# dozimetr-1layer.net
KiCad netlist of a schematic drawn in EAGLE
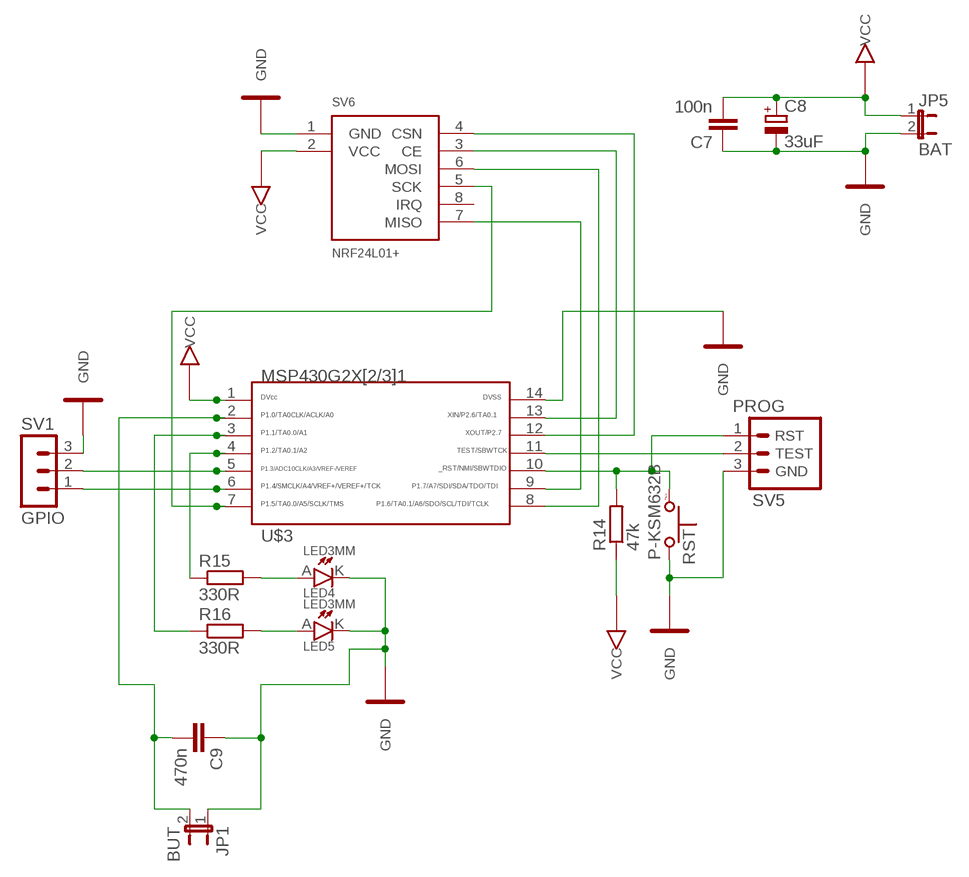
[diagram p0: schematic, sheet 1]

(export (version "E")
  (design (tool "Eeschema 10.0.6"))
  (components
    (comp (ref "C7")
      (value "100n")
      (footprint "eagle-import:C0805")
      (libsource (lib "eagle-import") (part "C-EUC0805"))
    )
    (comp (ref "C8")
      (value "33uF")
      (footprint "eagle-import:E2,5-6E")
      (libsource (lib "eagle-import") (part "CPOL-EUE2,5-6E"))
    )
    (comp (ref "C9")
      (value "470n")
      (footprint "eagle-import:C0805K")
      (libsource (lib "eagle-import") (part "C-EUC0805K"))
    )
    (comp (ref "JP1")
      (value "BUT")
      (footprint "eagle-import:JP1")
      (libsource (lib "eagle-import") (part "JP1E"))
    )
    (comp (ref "JP5")
      (value "BAT")
      (footprint "eagle-import:JP1")
      (libsource (lib "eagle-import") (part "JP1E"))
    )
    (comp (ref "LED4")
      (value "LED3MM")
      (footprint "eagle-import:LED3MM")
      (libsource (lib "eagle-import") (part "LED3MM"))
    )
    (comp (ref "LED5")
      (value "LED3MM")
      (footprint "eagle-import:LED3MM")
      (libsource (lib "eagle-import") (part "LED3MM"))
    )
    (comp (ref "R14")
      (value "47k")
      (footprint "eagle-import:R0805")
      (libsource (lib "eagle-import") (part "R-EU_R0805"))
    )
    (comp (ref "R15")
      (value "330R")
      (footprint "eagle-import:R0805")
      (libsource (lib "eagle-import") (part "R-EU_R0805"))
    )
    (comp (ref "R16")
      (value "330R")
      (footprint "eagle-import:R0805")
      (libsource (lib "eagle-import") (part "R-EU_R0805"))
    )
    (comp (ref "RST")
      (value "P-KSM632B")
      (footprint "eagle-import:P-KSM632B")
      (libsource (lib "eagle-import") (part "P-KSM632B"))
    )
    (comp (ref "SV1")
      (value "GPIO")
      (footprint "eagle-import:MA03-1")
      (libsource (lib "eagle-import") (part "con-lstb_MA03-1"))
    )
    (comp (ref "SV5")
      (value "PROG")
      (footprint "eagle-import:MA03-1")
      (libsource (lib "eagle-import") (part "MA03-1"))
    )
    (comp (ref "SV6")
      (value "NRF24L01+")
      (footprint "eagle-import:NRF24L01_MOD")
      (libsource (lib "eagle-import") (part "NRF24L01_MOD"))
    )
    (comp (ref "U$3")
      (value "G2X[2/3]1---PW14")
      (footprint "eagle-import:PW14")
      (libsource (lib "eagle-import") (part "G2X[2/3]1---PW14"))
    )
  )
  (nets
    (net (code "1") (name "GND") (class "Default")
      (node (ref "C7") (pin "1") (pinfunction "1_1") (pintype "passive"))
      (node (ref "C8") (pin "-") (pinfunction "-_-") (pintype "passive"))
      (node (ref "C9") (pin "1") (pinfunction "1_1") (pintype "passive"))
      (node (ref "JP1") (pin "1") (pinfunction "1_1") (pintype "passive"))
      (node (ref "JP5") (pin "2") (pinfunction "2_2") (pintype "passive"))
      (node (ref "LED4") (pin "K") (pinfunction "C_K") (pintype "bidirectional"))
      (node (ref "LED5") (pin "K") (pinfunction "C_K") (pintype "bidirectional"))
      (node (ref "RST") (pin "2") (pinfunction "2_2") (pintype "passive"))
      (node (ref "SV1") (pin "3") (pinfunction "3_3") (pintype "passive"))
      (node (ref "SV5") (pin "3") (pinfunction "GND_3") (pintype "passive"))
      (node (ref "SV6") (pin "1") (pinfunction "GND_1") (pintype "bidirectional"))
      (node (ref "U$3") (pin "14") (pinfunction "14_14") (pintype "bidirectional"))
    )
    (net (code "2") (name "Net-(C9-Pad2)") (class "Default")
      (node (ref "C9") (pin "2") (pinfunction "2_2") (pintype "passive"))
      (node (ref "JP1") (pin "2") (pinfunction "2_2") (pintype "passive"))
      (node (ref "U$3") (pin "2") (pinfunction "2_2") (pintype "bidirectional"))
    )
    (net (code "3") (name "Net-(LED4-PadA)") (class "Default")
      (node (ref "LED4") (pin "A") (pinfunction "A_A") (pintype "bidirectional"))
      (node (ref "R15") (pin "2") (pinfunction "2_2") (pintype "passive"))
    )
    (net (code "4") (name "Net-(LED5-PadA)") (class "Default")
      (node (ref "LED5") (pin "A") (pinfunction "A_A") (pintype "bidirectional"))
      (node (ref "R16") (pin "2") (pinfunction "2_2") (pintype "passive"))
    )
    (net (code "5") (name "Net-(R15-Pad1)") (class "Default")
      (node (ref "R15") (pin "1") (pinfunction "1_1") (pintype "passive"))
      (node (ref "U$3") (pin "4") (pinfunction "4_4") (pintype "bidirectional"))
    )
    (net (code "6") (name "Net-(R16-Pad1)") (class "Default")
      (node (ref "R16") (pin "1") (pinfunction "1_1") (pintype "passive"))
      (node (ref "U$3") (pin "3") (pinfunction "3_3") (pintype "bidirectional"))
    )
    (net (code "7") (name "Net-(SV1-Pad1)") (class "Default")
      (node (ref "SV1") (pin "1") (pinfunction "1_1") (pintype "passive"))
      (node (ref "U$3") (pin "6") (pinfunction "6_6") (pintype "bidirectional"))
    )
    (net (code "8") (name "Net-(SV1-Pad2)") (class "Default")
      (node (ref "SV1") (pin "2") (pinfunction "2_2") (pintype "passive"))
      (node (ref "U$3") (pin "5") (pinfunction "5_5") (pintype "bidirectional"))
    )
    (net (code "9") (name "Net-(SV5-RST)") (class "Default")
      (node (ref "R14") (pin "2") (pinfunction "2_2") (pintype "passive"))
      (node (ref "RST") (pin "1") (pinfunction "1_1") (pintype "passive"))
      (node (ref "SV5") (pin "1") (pinfunction "RST_1") (pintype "passive"))
      (node (ref "U$3") (pin "10") (pinfunction "10_10") (pintype "bidirectional"))
    )
    (net (code "10") (name "Net-(SV5-TEST)") (class "Default")
      (node (ref "SV5") (pin "2") (pinfunction "TEST_2") (pintype "passive"))
      (node (ref "U$3") (pin "11") (pinfunction "11_11") (pintype "bidirectional"))
    )
    (net (code "11") (name "Net-(SV6-CE)") (class "Default")
      (node (ref "SV6") (pin "3") (pinfunction "CE_3") (pintype "bidirectional"))
      (node (ref "U$3") (pin "13") (pinfunction "13_13") (pintype "bidirectional"))
    )
    (net (code "12") (name "Net-(SV6-CSN)") (class "Default")
      (node (ref "SV6") (pin "4") (pinfunction "CSN_4") (pintype "bidirectional"))
      (node (ref "U$3") (pin "12") (pinfunction "12_12") (pintype "bidirectional"))
    )
    (net (code "13") (name "Net-(SV6-MISO)") (class "Default")
      (node (ref "SV6") (pin "7") (pinfunction "MISO_7") (pintype "bidirectional"))
      (node (ref "U$3") (pin "9") (pinfunction "9_9") (pintype "bidirectional"))
    )
    (net (code "14") (name "Net-(SV6-MOSI)") (class "Default")
      (node (ref "SV6") (pin "6") (pinfunction "MOSI_6") (pintype "bidirectional"))
      (node (ref "U$3") (pin "8") (pinfunction "8_8") (pintype "bidirectional"))
    )
    (net (code "15") (name "Net-(SV6-SCK)") (class "Default")
      (node (ref "SV6") (pin "5") (pinfunction "SCK_5") (pintype "bidirectional"))
      (node (ref "U$3") (pin "7") (pinfunction "7_7") (pintype "bidirectional"))
    )
    (net (code "16") (name "VCC") (class "Default")
      (node (ref "C7") (pin "2") (pinfunction "2_2") (pintype "passive"))
      (node (ref "C8") (pin "+") (pinfunction "+_+") (pintype "passive"))
      (node (ref "JP5") (pin "1") (pinfunction "1_1") (pintype "passive"))
      (node (ref "R14") (pin "1") (pinfunction "1_1") (pintype "passive"))
      (node (ref "SV6") (pin "2") (pinfunction "VCC_2") (pintype "bidirectional"))
      (node (ref "U$3") (pin "1") (pinfunction "1_1") (pintype "bidirectional"))
    )
    (net (code "17") (name "unconnected-(SV6-IRQ-Pad8)") (class "Default")
      (node (ref "SV6") (pin "8") (pinfunction "IRQ_8") (pintype "bidirectional"))
    )
  )
)
